# gateInBreakout.net
KiCad netlist of a schematic drawn in EAGLE
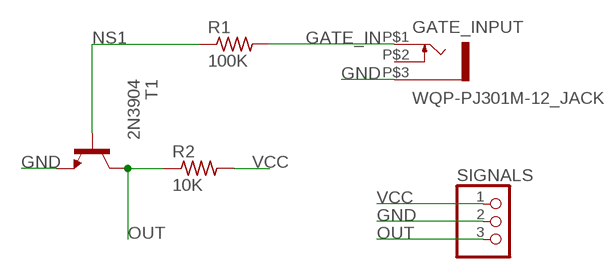
[diagram p0: schematic, sheet 1]

(export (version "E")
  (design (tool "Eeschema 10.0.6"))
  (components
    (comp (ref "GATE_INPUT")
      (value "WQP-PJ301M-12_JACK")
      (footprint "eagle-import:WQP-PJ301M-12_JACK")
      (libsource (lib "eagle-import") (part "WQP-PJ301M-12_JACK"))
    )
    (comp (ref "R1")
      (value "100K")
      (footprint "eagle-import:0207_9")
      (libsource (lib "eagle-import") (part "R-US_0207/9"))
    )
    (comp (ref "R2")
      (value "10K")
      (footprint "eagle-import:0207_9")
      (libsource (lib "eagle-import") (part "R-US_0207/9"))
    )
    (comp (ref "SIGNALS")
      (value "PINHD-1X3")
      (footprint "eagle-import:1X03")
      (libsource (lib "eagle-import") (part "PINHD-1X3"))
    )
    (comp (ref "T1")
      (value "2N3904")
      (footprint "eagle-import:TO92")
      (libsource (lib "eagle-import") (part "2N3904"))
    )
  )
  (nets
    (net (code "1") (name "/GATE_IN") (class "Default")
      (node (ref "GATE_INPUT") (pin "P$1") (pinfunction "2_P$1") (pintype "passive"))
      (node (ref "R1") (pin "2") (pinfunction "2_2") (pintype "passive"))
    )
    (net (code "2") (name "/GND") (class "Default")
      (node (ref "GATE_INPUT") (pin "P$3") (pinfunction "1_P$3") (pintype "passive"))
      (node (ref "SIGNALS") (pin "2") (pinfunction "2_2") (pintype "passive"))
      (node (ref "T1") (pin "3") (pinfunction "E_3") (pintype "passive"))
    )
    (net (code "3") (name "/NS1") (class "Default")
      (node (ref "R1") (pin "1") (pinfunction "1_1") (pintype "passive"))
      (node (ref "T1") (pin "2") (pinfunction "B_2") (pintype "passive"))
    )
    (net (code "4") (name "/OUT") (class "Default")
      (node (ref "R2") (pin "1") (pinfunction "1_1") (pintype "passive"))
      (node (ref "SIGNALS") (pin "3") (pinfunction "3_3") (pintype "passive"))
      (node (ref "T1") (pin "1") (pinfunction "C_1") (pintype "passive"))
    )
    (net (code "5") (name "/VCC") (class "Default")
      (node (ref "R2") (pin "2") (pinfunction "2_2") (pintype "passive"))
      (node (ref "SIGNALS") (pin "1") (pinfunction "1_1") (pintype "passive"))
    )
    (net (code "6") (name "unconnected-(GATE_INPUT-3-PadP$2)") (class "Default")
      (node (ref "GATE_INPUT") (pin "P$2") (pinfunction "3_P$2") (pintype "passive"))
    )
  )
)
